# axiom_beta_interface_dummy_v0_8.net
KiCad netlist of a schematic drawn in EAGLE
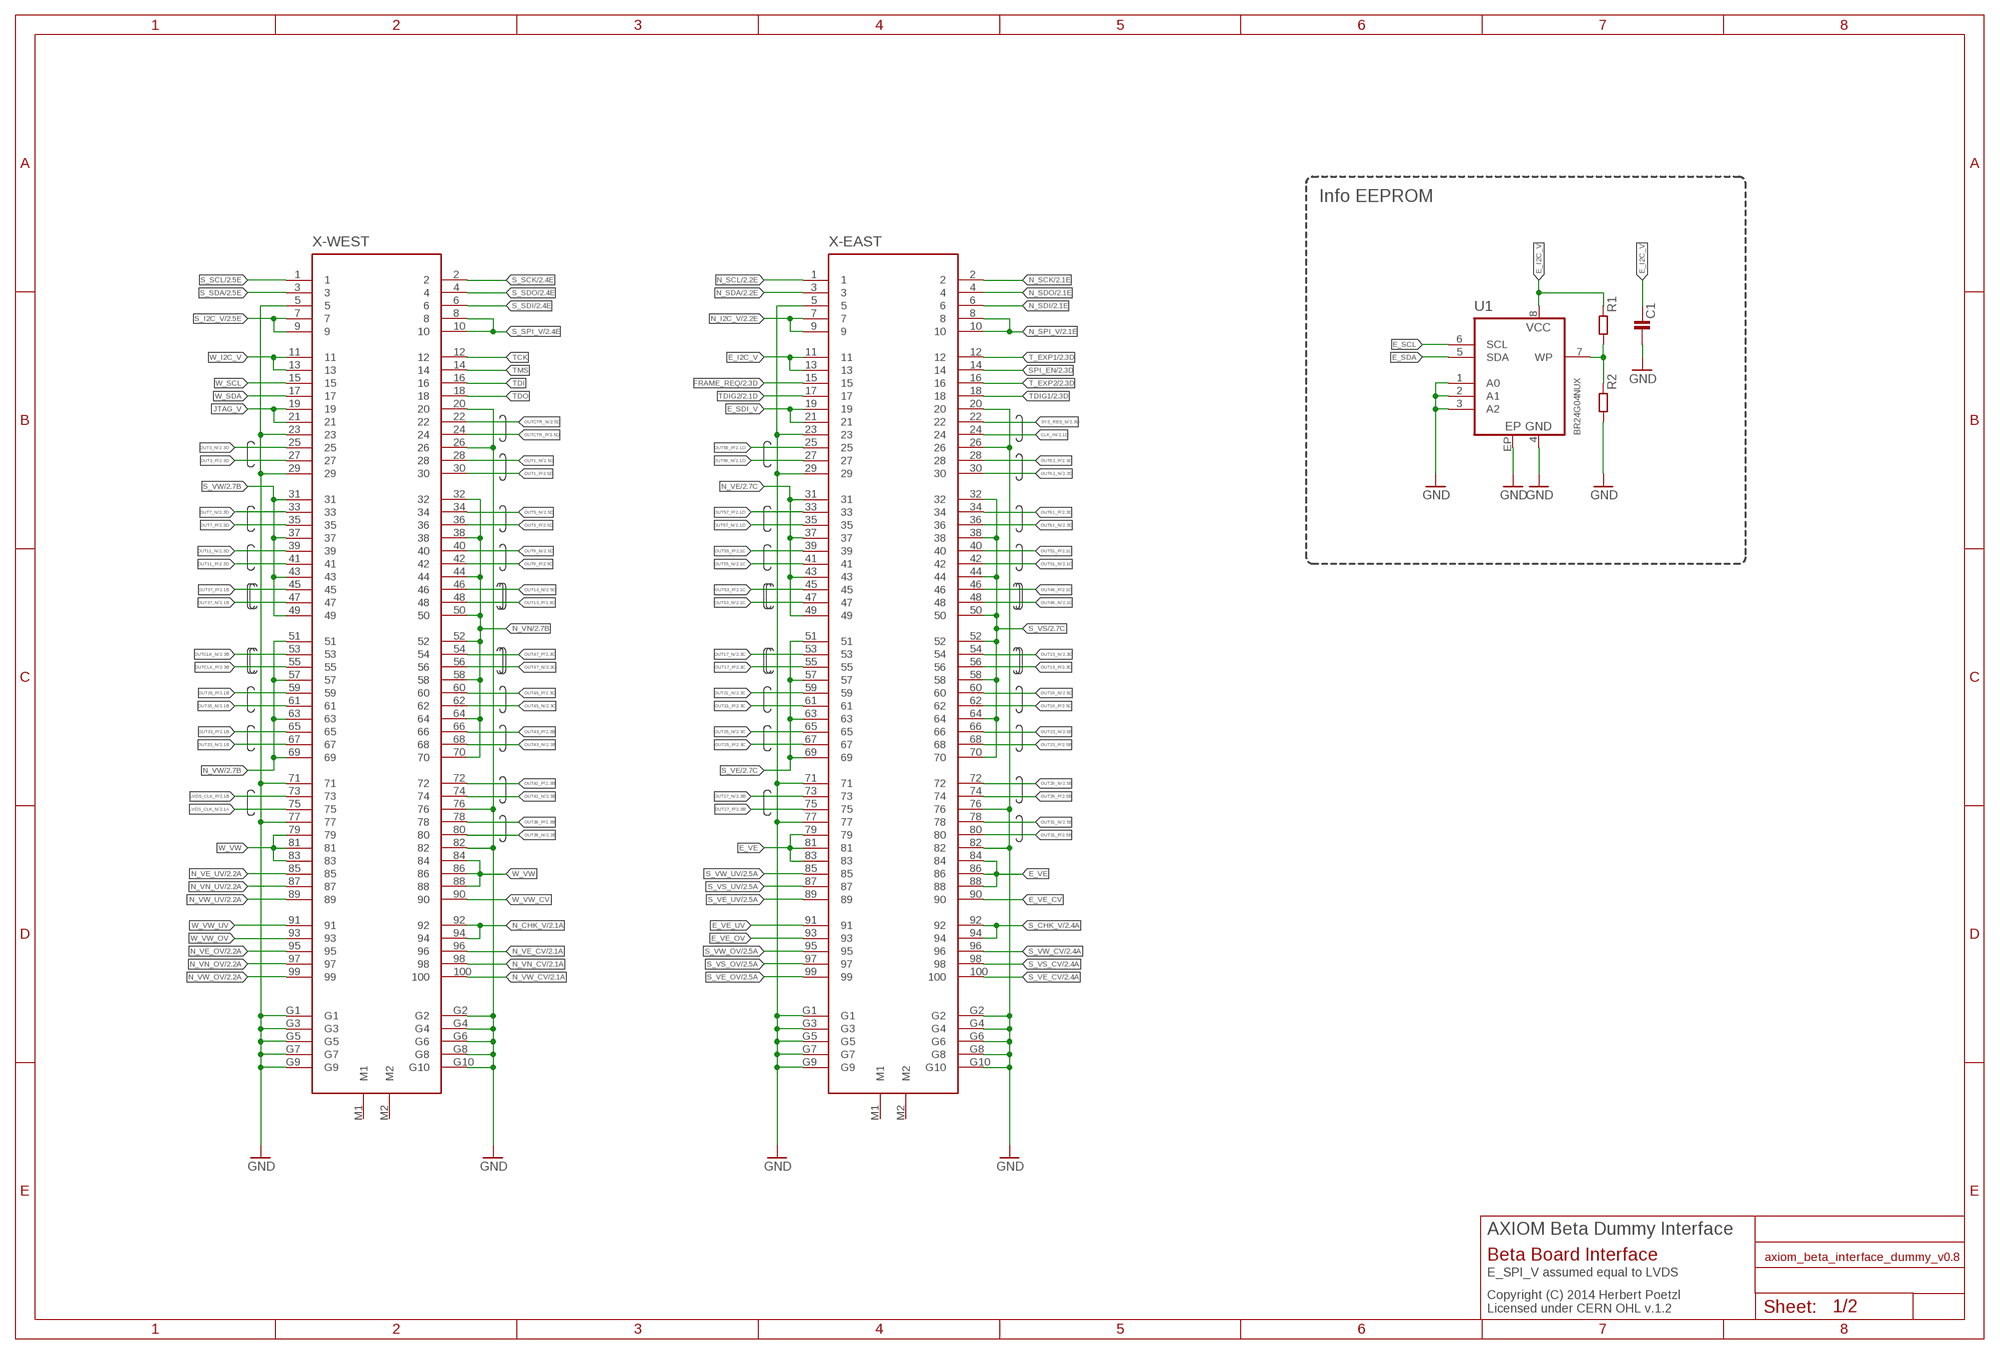
[diagram p0: schematic, sheet 1]
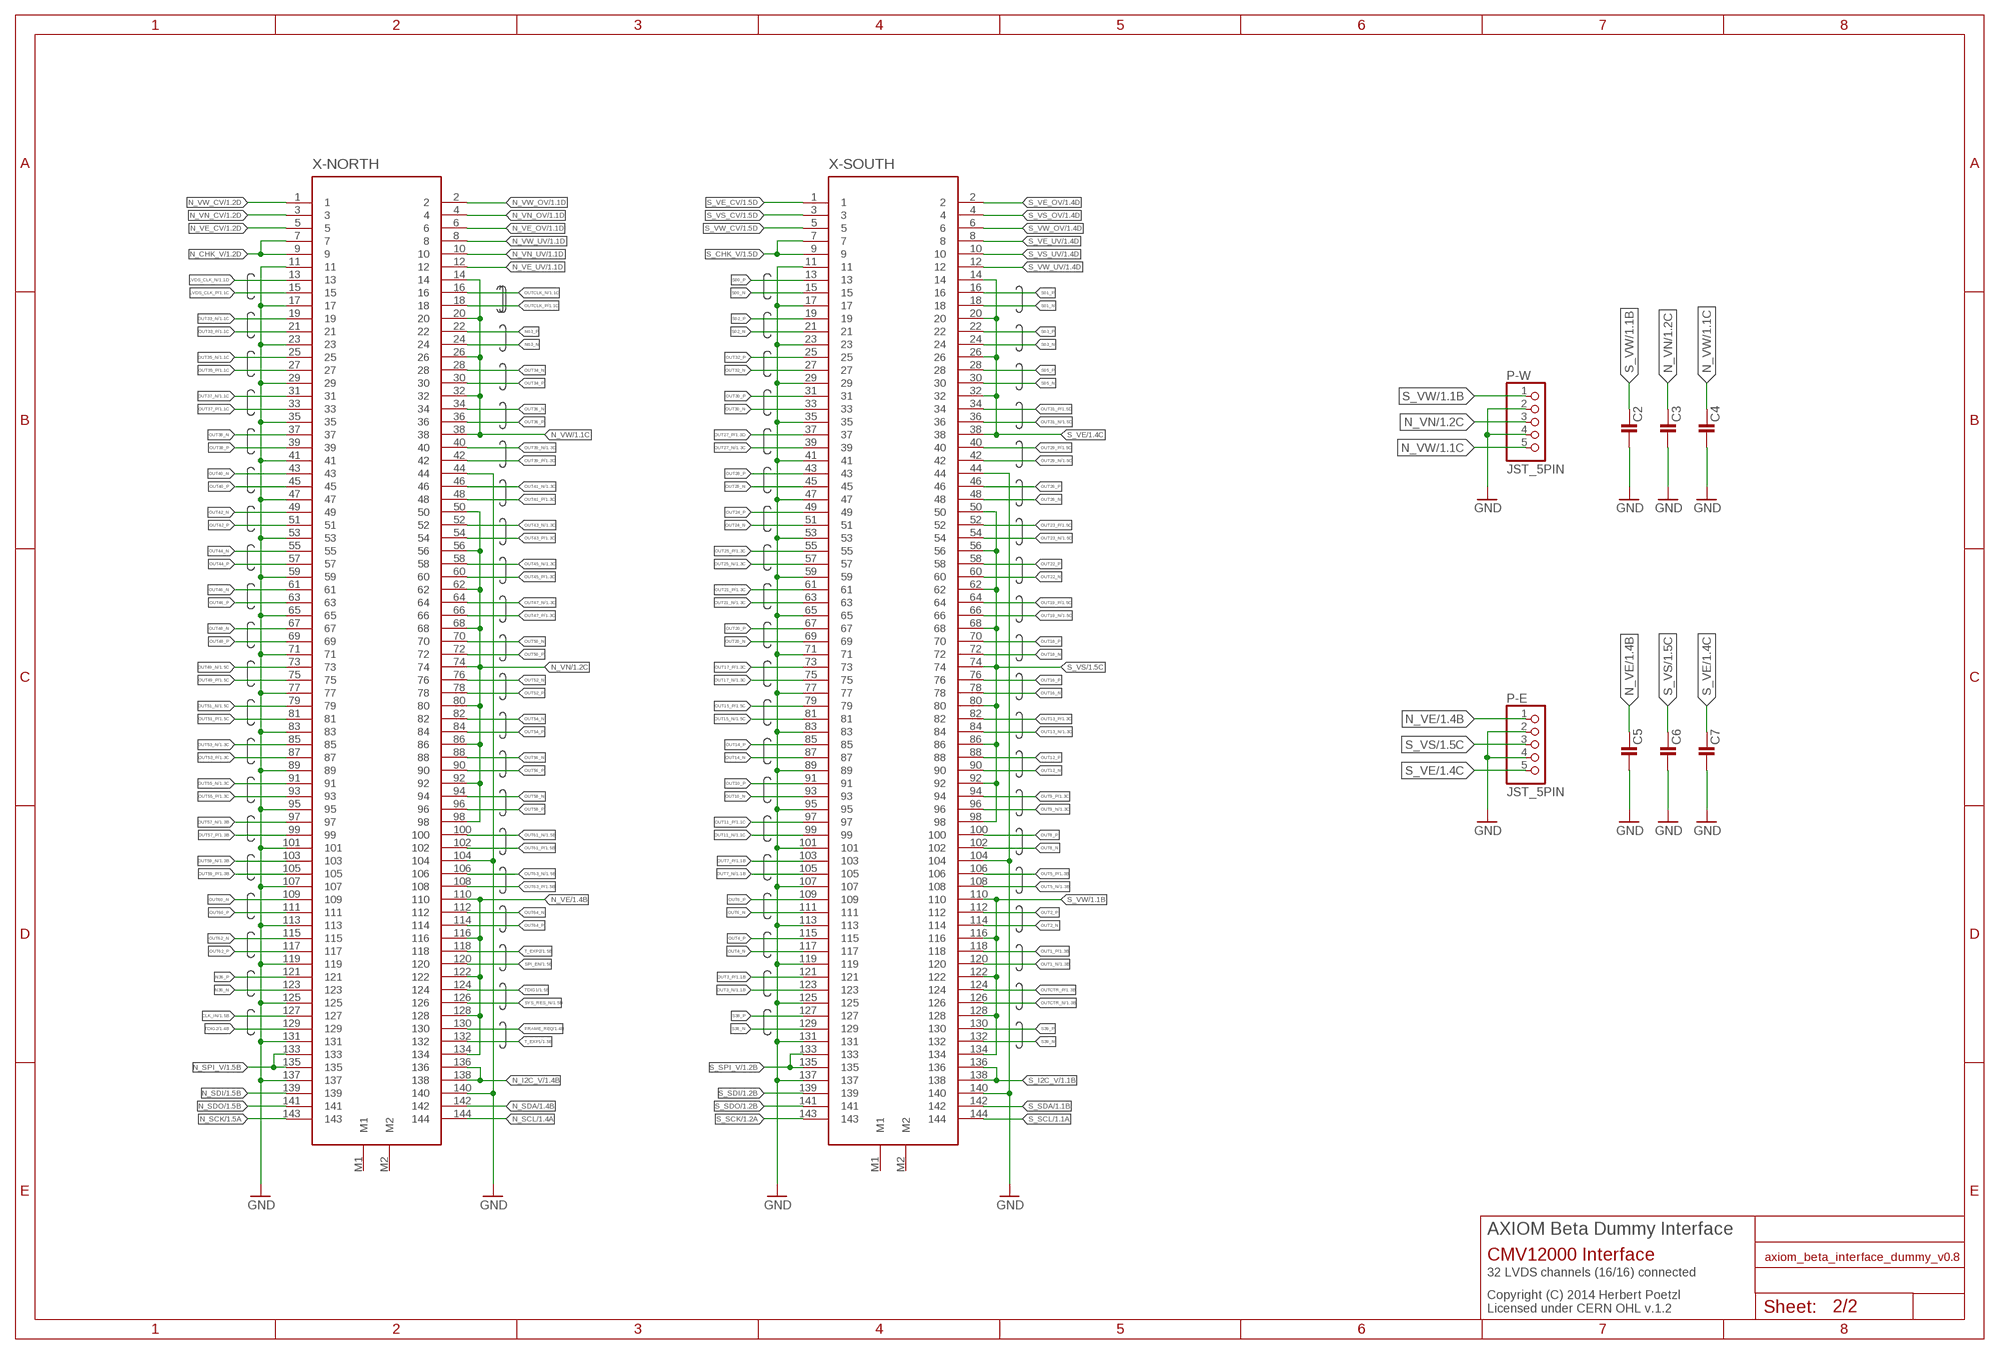
[diagram p1: schematic, sheet 2]

(export (version "E")
  (design (tool "Eeschema 10.0.6"))
  (components
    (comp (ref "C2")
      (value "C1206-B")
      (footprint "eagle-import:1206-B")
      (libsource (lib "eagle-import") (part "C1206-B"))
    )
    (comp (ref "C3")
      (value "C1206-B")
      (footprint "eagle-import:1206-B")
      (libsource (lib "eagle-import") (part "C1206-B"))
    )
    (comp (ref "C4")
      (value "C1206-B")
      (footprint "eagle-import:1206-B")
      (libsource (lib "eagle-import") (part "C1206-B"))
    )
    (comp (ref "C5")
      (value "C1206-B")
      (footprint "eagle-import:1206-B")
      (libsource (lib "eagle-import") (part "C1206-B"))
    )
    (comp (ref "C6")
      (value "C1206-B")
      (footprint "eagle-import:1206-B")
      (libsource (lib "eagle-import") (part "C1206-B"))
    )
    (comp (ref "C7")
      (value "C1206-B")
      (footprint "eagle-import:1206-B")
      (libsource (lib "eagle-import") (part "C1206-B"))
    )
    (comp (ref "P-E")
      (value "JST_5PIN")
      (footprint "eagle-import:JST-PH-5-SMT-RA")
      (libsource (lib "eagle-import") (part "JST_5PIN"))
    )
    (comp (ref "P-W")
      (value "JST_5PIN")
      (footprint "eagle-import:JST-PH-5-SMT-RA")
      (libsource (lib "eagle-import") (part "JST_5PIN"))
    )
    (comp (ref "X-NORTH")
      (value "FX10-144S")
      (footprint "eagle-import:FX10A-144S")
      (libsource (lib "eagle-import") (part "FX10-144S"))
    )
    (comp (ref "X-SOUTH")
      (value "FX10-144S")
      (footprint "eagle-import:FX10A-144S")
      (libsource (lib "eagle-import") (part "FX10-144S"))
    )
    (comp (ref "C1")
      (value "C0402-B")
      (footprint "eagle-import:0402-B")
      (libsource (lib "eagle-import") (part "C0402-B"))
    )
    (comp (ref "R1")
      (value "R0402-B")
      (footprint "eagle-import:0402-B")
      (libsource (lib "eagle-import") (part "R0402-B"))
    )
    (comp (ref "R2")
      (value "R0402-B")
      (footprint "eagle-import:0402-B")
      (libsource (lib "eagle-import") (part "R0402-B"))
    )
    (comp (ref "U1")
      (value "BR24G04NUX")
      (footprint "eagle-import:DFN200X300X100-9N")
      (libsource (lib "eagle-import") (part "BR24G04NUX"))
    )
    (comp (ref "X-EAST")
      (value "FX10-100/10P")
      (footprint "eagle-import:FX10A-100P_10")
      (libsource (lib "eagle-import") (part "FX10-100/10P"))
    )
    (comp (ref "X-WEST")
      (value "FX10-100/10P")
      (footprint "eagle-import:FX10A-100P_10")
      (libsource (lib "eagle-import") (part "FX10-100/10P"))
    )
  )
  (nets
    (net (code "1") (name "CLK_IN") (class "Default")
      (node (ref "X-EAST") (pin "24") (pinfunction "24_24") (pintype "bidirectional"))
      (node (ref "X-NORTH") (pin "127") (pinfunction "127_127") (pintype "bidirectional"))
    )
    (net (code "2") (name "E_I2C_V") (class "Default")
      (node (ref "C1") (pin "1") (pinfunction "1_1") (pintype "passive"))
      (node (ref "R1") (pin "1") (pinfunction "1_1") (pintype "passive"))
      (node (ref "U1") (pin "8") (pinfunction "VCC_8") (pintype "power_in"))
      (node (ref "X-EAST") (pin "11") (pinfunction "11_11") (pintype "bidirectional"))
      (node (ref "X-EAST") (pin "13") (pinfunction "13_13") (pintype "bidirectional"))
    )
    (net (code "3") (name "E_SCL") (class "Default")
      (node (ref "U1") (pin "6") (pinfunction "SCL_6") (pintype "input"))
    )
    (net (code "4") (name "E_SDA") (class "Default")
      (node (ref "U1") (pin "5") (pinfunction "SDA_5") (pintype "bidirectional"))
    )
    (net (code "5") (name "E_SDI_V") (class "Default")
      (node (ref "X-EAST") (pin "19") (pinfunction "19_19") (pintype "bidirectional"))
      (node (ref "X-EAST") (pin "21") (pinfunction "21_21") (pintype "bidirectional"))
    )
    (net (code "6") (name "E_VE") (class "Default")
      (node (ref "X-EAST") (pin "79") (pinfunction "79_79") (pintype "bidirectional"))
      (node (ref "X-EAST") (pin "81") (pinfunction "81_81") (pintype "bidirectional"))
      (node (ref "X-EAST") (pin "83") (pinfunction "83_83") (pintype "bidirectional"))
      (node (ref "X-EAST") (pin "84") (pinfunction "84_84") (pintype "bidirectional"))
      (node (ref "X-EAST") (pin "86") (pinfunction "86_86") (pintype "bidirectional"))
      (node (ref "X-EAST") (pin "88") (pinfunction "88_88") (pintype "bidirectional"))
    )
    (net (code "7") (name "E_VE_CV") (class "Default")
      (node (ref "X-EAST") (pin "90") (pinfunction "90_90") (pintype "bidirectional"))
    )
    (net (code "8") (name "E_VE_OV") (class "Default")
      (node (ref "X-EAST") (pin "93") (pinfunction "93_93") (pintype "bidirectional"))
    )
    (net (code "9") (name "E_VE_UV") (class "Default")
      (node (ref "X-EAST") (pin "91") (pinfunction "91_91") (pintype "bidirectional"))
    )
    (net (code "10") (name "FRAME_REQ") (class "Default")
      (node (ref "X-EAST") (pin "15") (pinfunction "15_15") (pintype "bidirectional"))
      (node (ref "X-NORTH") (pin "130") (pinfunction "130_130") (pintype "bidirectional"))
    )
    (net (code "11") (name "GND") (class "Default")
      (node (ref "C1") (pin "2") (pinfunction "2_2") (pintype "passive"))
      (node (ref "C2") (pin "2") (pinfunction "2_2") (pintype "passive"))
      (node (ref "C3") (pin "2") (pinfunction "2_2") (pintype "passive"))
      (node (ref "C4") (pin "2") (pinfunction "2_2") (pintype "passive"))
      (node (ref "C5") (pin "2") (pinfunction "2_2") (pintype "passive"))
      (node (ref "C6") (pin "2") (pinfunction "2_2") (pintype "passive"))
      (node (ref "C7") (pin "2") (pinfunction "2_2") (pintype "passive"))
      (node (ref "P-E") (pin "2") (pinfunction "2_2") (pintype "passive"))
      (node (ref "P-E") (pin "4") (pinfunction "4_4") (pintype "passive"))
      (node (ref "P-W") (pin "2") (pinfunction "2_2") (pintype "passive"))
      (node (ref "P-W") (pin "4") (pinfunction "4_4") (pintype "passive"))
      (node (ref "R2") (pin "2") (pinfunction "2_2") (pintype "passive"))
      (node (ref "U1") (pin "1") (pinfunction "A0_1") (pintype "input"))
      (node (ref "U1") (pin "2") (pinfunction "A1_2") (pintype "input"))
      (node (ref "U1") (pin "3") (pinfunction "A2_3") (pintype "input"))
      (node (ref "U1") (pin "4") (pinfunction "GND_4") (pintype "passive"))
      (node (ref "U1") (pin "EP") (pinfunction "EP_EP") (pintype "passive"))
      (node (ref "X-EAST") (pin "20") (pinfunction "20_20") (pintype "bidirectional"))
      (node (ref "X-EAST") (pin "23") (pinfunction "23_23") (pintype "bidirectional"))
      (node (ref "X-EAST") (pin "26") (pinfunction "26_26") (pintype "bidirectional"))
      (node (ref "X-EAST") (pin "29") (pinfunction "29_29") (pintype "bidirectional"))
      (node (ref "X-EAST") (pin "5") (pinfunction "5_5") (pintype "bidirectional"))
      (node (ref "X-EAST") (pin "71") (pinfunction "71_71") (pintype "bidirectional"))
      (node (ref "X-EAST") (pin "76") (pinfunction "76_76") (pintype "bidirectional"))
      (node (ref "X-EAST") (pin "77") (pinfunction "77_77") (pintype "bidirectional"))
      (node (ref "X-EAST") (pin "82") (pinfunction "82_82") (pintype "bidirectional"))
      (node (ref "X-EAST") (pin "G1") (pinfunction "G1_G1") (pintype "bidirectional"))
      (node (ref "X-EAST") (pin "G10") (pinfunction "G10_G10") (pintype "bidirectional"))
      (node (ref "X-EAST") (pin "G2") (pinfunction "G2_G2") (pintype "bidirectional"))
      (node (ref "X-EAST") (pin "G3") (pinfunction "G3_G3") (pintype "bidirectional"))
      (node (ref "X-EAST") (pin "G4") (pinfunction "G4_G4") (pintype "bidirectional"))
      (node (ref "X-EAST") (pin "G5") (pinfunction "G5_G5") (pintype "bidirectional"))
      (node (ref "X-EAST") (pin "G6") (pinfunction "G6_G6") (pintype "bidirectional"))
      (node (ref "X-EAST") (pin "G7") (pinfunction "G7_G7") (pintype "bidirectional"))
      (node (ref "X-EAST") (pin "G8") (pinfunction "G8_G8") (pintype "bidirectional"))
      (node (ref "X-EAST") (pin "G9") (pinfunction "G9_G9") (pintype "bidirectional"))
      (node (ref "X-NORTH") (pin "101") (pinfunction "101_101") (pintype "bidirectional"))
      (node (ref "X-NORTH") (pin "104") (pinfunction "104_104") (pintype "bidirectional"))
      (node (ref "X-NORTH") (pin "107") (pinfunction "107_107") (pintype "bidirectional"))
      (node (ref "X-NORTH") (pin "11") (pinfunction "11_11") (pintype "bidirectional"))
      (node (ref "X-NORTH") (pin "113") (pinfunction "113_113") (pintype "bidirectional"))
      (node (ref "X-NORTH") (pin "119") (pinfunction "119_119") (pintype "bidirectional"))
      (node (ref "X-NORTH") (pin "125") (pinfunction "125_125") (pintype "bidirectional"))
      (node (ref "X-NORTH") (pin "131") (pinfunction "131_131") (pintype "bidirectional"))
      (node (ref "X-NORTH") (pin "137") (pinfunction "137_137") (pintype "bidirectional"))
      (node (ref "X-NORTH") (pin "140") (pinfunction "140_140") (pintype "bidirectional"))
      (node (ref "X-NORTH") (pin "17") (pinfunction "17_17") (pintype "bidirectional"))
      (node (ref "X-NORTH") (pin "23") (pinfunction "23_23") (pintype "bidirectional"))
      (node (ref "X-NORTH") (pin "29") (pinfunction "29_29") (pintype "bidirectional"))
      (node (ref "X-NORTH") (pin "35") (pinfunction "35_35") (pintype "bidirectional"))
      (node (ref "X-NORTH") (pin "41") (pinfunction "41_41") (pintype "bidirectional"))
      (node (ref "X-NORTH") (pin "44") (pinfunction "44_44") (pintype "bidirectional"))
      (node (ref "X-NORTH") (pin "47") (pinfunction "47_47") (pintype "bidirectional"))
      (node (ref "X-NORTH") (pin "53") (pinfunction "53_53") (pintype "bidirectional"))
      (node (ref "X-NORTH") (pin "59") (pinfunction "59_59") (pintype "bidirectional"))
      (node (ref "X-NORTH") (pin "65") (pinfunction "65_65") (pintype "bidirectional"))
      (node (ref "X-NORTH") (pin "71") (pinfunction "71_71") (pintype "bidirectional"))
      (node (ref "X-NORTH") (pin "77") (pinfunction "77_77") (pintype "bidirectional"))
      (node (ref "X-NORTH") (pin "83") (pinfunction "83_83") (pintype "bidirectional"))
      (node (ref "X-NORTH") (pin "89") (pinfunction "89_89") (pintype "bidirectional"))
      (node (ref "X-NORTH") (pin "95") (pinfunction "95_95") (pintype "bidirectional"))
      (node (ref "X-SOUTH") (pin "101") (pinfunction "101_101") (pintype "bidirectional"))
      (node (ref "X-SOUTH") (pin "104") (pinfunction "104_104") (pintype "bidirectional"))
      (node (ref "X-SOUTH") (pin "107") (pinfunction "107_107") (pintype "bidirectional"))
      (node (ref "X-SOUTH") (pin "11") (pinfunction "11_11") (pintype "bidirectional"))
      (node (ref "X-SOUTH") (pin "113") (pinfunction "113_113") (pintype "bidirectional"))
      (node (ref "X-SOUTH") (pin "119") (pinfunction "119_119") (pintype "bidirectional"))
      (node (ref "X-SOUTH") (pin "125") (pinfunction "125_125") (pintype "bidirectional"))
      (node (ref "X-SOUTH") (pin "131") (pinfunction "131_131") (pintype "bidirectional"))
      (node (ref "X-SOUTH") (pin "137") (pinfunction "137_137") (pintype "bidirectional"))
      (node (ref "X-SOUTH") (pin "140") (pinfunction "140_140") (pintype "bidirectional"))
      (node (ref "X-SOUTH") (pin "17") (pinfunction "17_17") (pintype "bidirectional"))
      (node (ref "X-SOUTH") (pin "23") (pinfunction "23_23") (pintype "bidirectional"))
      (node (ref "X-SOUTH") (pin "29") (pinfunction "29_29") (pintype "bidirectional"))
      (node (ref "X-SOUTH") (pin "35") (pinfunction "35_35") (pintype "bidirectional"))
      (node (ref "X-SOUTH") (pin "41") (pinfunction "41_41") (pintype "bidirectional"))
      (node (ref "X-SOUTH") (pin "44") (pinfunction "44_44") (pintype "bidirectional"))
      (node (ref "X-SOUTH") (pin "47") (pinfunction "47_47") (pintype "bidirectional"))
      (node (ref "X-SOUTH") (pin "53") (pinfunction "53_53") (pintype "bidirectional"))
      (node (ref "X-SOUTH") (pin "59") (pinfunction "59_59") (pintype "bidirectional"))
      (node (ref "X-SOUTH") (pin "65") (pinfunction "65_65") (pintype "bidirectional"))
      (node (ref "X-SOUTH") (pin "71") (pinfunction "71_71") (pintype "bidirectional"))
      (node (ref "X-SOUTH") (pin "77") (pinfunction "77_77") (pintype "bidirectional"))
      (node (ref "X-SOUTH") (pin "83") (pinfunction "83_83") (pintype "bidirectional"))
      (node (ref "X-SOUTH") (pin "89") (pinfunction "89_89") (pintype "bidirectional"))
      (node (ref "X-SOUTH") (pin "95") (pinfunction "95_95") (pintype "bidirectional"))
      (node (ref "X-WEST") (pin "20") (pinfunction "20_20") (pintype "bidirectional"))
      (node (ref "X-WEST") (pin "23") (pinfunction "23_23") (pintype "bidirectional"))
      (node (ref "X-WEST") (pin "26") (pinfunction "26_26") (pintype "bidirectional"))
      (node (ref "X-WEST") (pin "29") (pinfunction "29_29") (pintype "bidirectional"))
      (node (ref "X-WEST") (pin "5") (pinfunction "5_5") (pintype "bidirectional"))
      (node (ref "X-WEST") (pin "71") (pinfunction "71_71") (pintype "bidirectional"))
      (node (ref "X-WEST") (pin "76") (pinfunction "76_76") (pintype "bidirectional"))
      (node (ref "X-WEST") (pin "77") (pinfunction "77_77") (pintype "bidirectional"))
      (node (ref "X-WEST") (pin "82") (pinfunction "82_82") (pintype "bidirectional"))
      (node (ref "X-WEST") (pin "G1") (pinfunction "G1_G1") (pintype "bidirectional"))
      (node (ref "X-WEST") (pin "G10") (pinfunction "G10_G10") (pintype "bidirectional"))
      (node (ref "X-WEST") (pin "G2") (pinfunction "G2_G2") (pintype "bidirectional"))
      (node (ref "X-WEST") (pin "G3") (pinfunction "G3_G3") (pintype "bidirectional"))
      (node (ref "X-WEST") (pin "G4") (pinfunction "G4_G4") (pintype "bidirectional"))
      (node (ref "X-WEST") (pin "G5") (pinfunction "G5_G5") (pintype "bidirectional"))
      (node (ref "X-WEST") (pin "G6") (pinfunction "G6_G6") (pintype "bidirectional"))
      (node (ref "X-WEST") (pin "G7") (pinfunction "G7_G7") (pintype "bidirectional"))
      (node (ref "X-WEST") (pin "G8") (pinfunction "G8_G8") (pintype "bidirectional"))
      (node (ref "X-WEST") (pin "G9") (pinfunction "G9_G9") (pintype "bidirectional"))
    )
    (net (code "12") (name "JTAG_V") (class "Default")
      (node (ref "X-WEST") (pin "19") (pinfunction "19_19") (pintype "bidirectional"))
      (node (ref "X-WEST") (pin "21") (pinfunction "21_21") (pintype "bidirectional"))
    )
    (net (code "13") (name "LVDS_CLK_N") (class "Default")
      (node (ref "X-NORTH") (pin "13") (pinfunction "13_13") (pintype "bidirectional"))
      (node (ref "X-WEST") (pin "75") (pinfunction "75_75") (pintype "bidirectional"))
    )
    (net (code "14") (name "LVDS_CLK_P") (class "Default")
      (node (ref "X-NORTH") (pin "15") (pinfunction "15_15") (pintype "bidirectional"))
      (node (ref "X-WEST") (pin "73") (pinfunction "73_73") (pintype "bidirectional"))
    )
    (net (code "15") (name "N03_N") (class "Default")
      (node (ref "X-NORTH") (pin "24") (pinfunction "24_24") (pintype "bidirectional"))
    )
    (net (code "16") (name "N03_P") (class "Default")
      (node (ref "X-NORTH") (pin "22") (pinfunction "22_22") (pintype "bidirectional"))
    )
    (net (code "17") (name "N36_N") (class "Default")
      (node (ref "X-NORTH") (pin "123") (pinfunction "123_123") (pintype "bidirectional"))
    )
    (net (code "18") (name "N36_P") (class "Default")
      (node (ref "X-NORTH") (pin "121") (pinfunction "121_121") (pintype "bidirectional"))
    )
    (net (code "19") (name "N_CHK_V") (class "Default")
      (node (ref "X-NORTH") (pin "7") (pinfunction "7_7") (pintype "bidirectional"))
      (node (ref "X-NORTH") (pin "9") (pinfunction "9_9") (pintype "bidirectional"))
      (node (ref "X-WEST") (pin "92") (pinfunction "92_92") (pintype "bidirectional"))
      (node (ref "X-WEST") (pin "94") (pinfunction "94_94") (pintype "bidirectional"))
    )
    (net (code "20") (name "N_I2C_V") (class "Default")
      (node (ref "X-EAST") (pin "7") (pinfunction "7_7") (pintype "bidirectional"))
      (node (ref "X-EAST") (pin "9") (pinfunction "9_9") (pintype "bidirectional"))
      (node (ref "X-NORTH") (pin "136") (pinfunction "136_136") (pintype "bidirectional"))
      (node (ref "X-NORTH") (pin "138") (pinfunction "138_138") (pintype "bidirectional"))
    )
    (net (code "21") (name "N_SCK") (class "Default")
      (node (ref "X-EAST") (pin "2") (pinfunction "2_2") (pintype "bidirectional"))
      (node (ref "X-NORTH") (pin "143") (pinfunction "143_143") (pintype "bidirectional"))
    )
    (net (code "22") (name "N_SCL") (class "Default")
      (node (ref "X-EAST") (pin "1") (pinfunction "1_1") (pintype "bidirectional"))
      (node (ref "X-NORTH") (pin "144") (pinfunction "144_144") (pintype "bidirectional"))
    )
    (net (code "23") (name "N_SDA") (class "Default")
      (node (ref "X-EAST") (pin "3") (pinfunction "3_3") (pintype "bidirectional"))
      (node (ref "X-NORTH") (pin "142") (pinfunction "142_142") (pintype "bidirectional"))
    )
    (net (code "24") (name "N_SDI") (class "Default")
      (node (ref "X-EAST") (pin "6") (pinfunction "6_6") (pintype "bidirectional"))
      (node (ref "X-NORTH") (pin "139") (pinfunction "139_139") (pintype "bidirectional"))
    )
    (net (code "25") (name "N_SDO") (class "Default")
      (node (ref "X-EAST") (pin "4") (pinfunction "4_4") (pintype "bidirectional"))
      (node (ref "X-NORTH") (pin "141") (pinfunction "141_141") (pintype "bidirectional"))
    )
    (net (code "26") (name "N_SPI_V") (class "Default")
      (node (ref "X-EAST") (pin "10") (pinfunction "10_10") (pintype "bidirectional"))
      (node (ref "X-EAST") (pin "8") (pinfunction "8_8") (pintype "bidirectional"))
      (node (ref "X-NORTH") (pin "133") (pinfunction "133_133") (pintype "bidirectional"))
      (node (ref "X-NORTH") (pin "135") (pinfunction "135_135") (pintype "bidirectional"))
    )
    (net (code "27") (name "N_VE") (class "Default")
      (node (ref "C5") (pin "1") (pinfunction "1_1") (pintype "passive"))
      (node (ref "P-E") (pin "1") (pinfunction "1_1") (pintype "passive"))
      (node (ref "X-EAST") (pin "31") (pinfunction "31_31") (pintype "bidirectional"))
      (node (ref "X-EAST") (pin "37") (pinfunction "37_37") (pintype "bidirectional"))
      (node (ref "X-EAST") (pin "43") (pinfunction "43_43") (pintype "bidirectional"))
      (node (ref "X-EAST") (pin "49") (pinfunction "49_49") (pintype "bidirectional"))
      (node (ref "X-NORTH") (pin "110") (pinfunction "110_110") (pintype "bidirectional"))
      (node (ref "X-NORTH") (pin "116") (pinfunction "116_116") (pintype "bidirectional"))
      (node (ref "X-NORTH") (pin "122") (pinfunction "122_122") (pintype "bidirectional"))
      (node (ref "X-NORTH") (pin "128") (pinfunction "128_128") (pintype "bidirectional"))
      (node (ref "X-NORTH") (pin "134") (pinfunction "134_134") (pintype "bidirectional"))
    )
    (net (code "28") (name "N_VE_CV") (class "Default")
      (node (ref "X-NORTH") (pin "5") (pinfunction "5_5") (pintype "bidirectional"))
      (node (ref "X-WEST") (pin "96") (pinfunction "96_96") (pintype "bidirectional"))
    )
    (net (code "29") (name "N_VE_OV") (class "Default")
      (node (ref "X-NORTH") (pin "6") (pinfunction "6_6") (pintype "bidirectional"))
      (node (ref "X-WEST") (pin "95") (pinfunction "95_95") (pintype "bidirectional"))
    )
    (net (code "30") (name "N_VE_UV") (class "Default")
      (node (ref "X-NORTH") (pin "12") (pinfunction "12_12") (pintype "bidirectional"))
      (node (ref "X-WEST") (pin "85") (pinfunction "85_85") (pintype "bidirectional"))
    )
    (net (code "31") (name "N_VN") (class "Default")
      (node (ref "C3") (pin "1") (pinfunction "1_1") (pintype "passive"))
      (node (ref "P-W") (pin "3") (pinfunction "3_3") (pintype "passive"))
      (node (ref "X-NORTH") (pin "50") (pinfunction "50_50") (pintype "bidirectional"))
      (node (ref "X-NORTH") (pin "56") (pinfunction "56_56") (pintype "bidirectional"))
      (node (ref "X-NORTH") (pin "62") (pinfunction "62_62") (pintype "bidirectional"))
      (node (ref "X-NORTH") (pin "68") (pinfunction "68_68") (pintype "bidirectional"))
      (node (ref "X-NORTH") (pin "74") (pinfunction "74_74") (pintype "bidirectional"))
      (node (ref "X-NORTH") (pin "80") (pinfunction "80_80") (pintype "bidirectional"))
      (node (ref "X-NORTH") (pin "86") (pinfunction "86_86") (pintype "bidirectional"))
      (node (ref "X-NORTH") (pin "92") (pinfunction "92_92") (pintype "bidirectional"))
      (node (ref "X-NORTH") (pin "98") (pinfunction "98_98") (pintype "bidirectional"))
      (node (ref "X-WEST") (pin "32") (pinfunction "32_32") (pintype "bidirectional"))
      (node (ref "X-WEST") (pin "38") (pinfunction "38_38") (pintype "bidirectional"))
      (node (ref "X-WEST") (pin "44") (pinfunction "44_44") (pintype "bidirectional"))
      (node (ref "X-WEST") (pin "50") (pinfunction "50_50") (pintype "bidirectional"))
      (node (ref "X-WEST") (pin "52") (pinfunction "52_52") (pintype "bidirectional"))
      (node (ref "X-WEST") (pin "58") (pinfunction "58_58") (pintype "bidirectional"))
      (node (ref "X-WEST") (pin "64") (pinfunction "64_64") (pintype "bidirectional"))
      (node (ref "X-WEST") (pin "70") (pinfunction "70_70") (pintype "bidirectional"))
    )
    (net (code "32") (name "N_VN_CV") (class "Default")
      (node (ref "X-NORTH") (pin "3") (pinfunction "3_3") (pintype "bidirectional"))
      (node (ref "X-WEST") (pin "98") (pinfunction "98_98") (pintype "bidirectional"))
    )
    (net (code "33") (name "N_VN_OV") (class "Default")
      (node (ref "X-NORTH") (pin "4") (pinfunction "4_4") (pintype "bidirectional"))
      (node (ref "X-WEST") (pin "97") (pinfunction "97_97") (pintype "bidirectional"))
    )
    (net (code "34") (name "N_VN_UV") (class "Default")
      (node (ref "X-NORTH") (pin "10") (pinfunction "10_10") (pintype "bidirectional"))
      (node (ref "X-WEST") (pin "87") (pinfunction "87_87") (pintype "bidirectional"))
    )
    (net (code "35") (name "N_VW") (class "Default")
      (node (ref "C4") (pin "1") (pinfunction "1_1") (pintype "passive"))
      (node (ref "P-W") (pin "5") (pinfunction "5_5") (pintype "passive"))
      (node (ref "X-NORTH") (pin "14") (pinfunction "14_14") (pintype "bidirectional"))
      (node (ref "X-NORTH") (pin "20") (pinfunction "20_20") (pintype "bidirectional"))
      (node (ref "X-NORTH") (pin "26") (pinfunction "26_26") (pintype "bidirectional"))
      (node (ref "X-NORTH") (pin "32") (pinfunction "32_32") (pintype "bidirectional"))
      (node (ref "X-NORTH") (pin "38") (pinfunction "38_38") (pintype "bidirectional"))
      (node (ref "X-WEST") (pin "51") (pinfunction "51_51") (pintype "bidirectional"))
      (node (ref "X-WEST") (pin "57") (pinfunction "57_57") (pintype "bidirectional"))
      (node (ref "X-WEST") (pin "63") (pinfunction "63_63") (pintype "bidirectional"))
      (node (ref "X-WEST") (pin "69") (pinfunction "69_69") (pintype "bidirectional"))
    )
    (net (code "36") (name "N_VW_CV") (class "Default")
      (node (ref "X-NORTH") (pin "1") (pinfunction "1_1") (pintype "bidirectional"))
      (node (ref "X-WEST") (pin "100") (pinfunction "100_100") (pintype "bidirectional"))
    )
    (net (code "37") (name "N_VW_OV") (class "Default")
      (node (ref "X-NORTH") (pin "2") (pinfunction "2_2") (pintype "bidirectional"))
      (node (ref "X-WEST") (pin "99") (pinfunction "99_99") (pintype "bidirectional"))
    )
    (net (code "38") (name "N_VW_UV") (class "Default")
      (node (ref "X-NORTH") (pin "8") (pinfunction "8_8") (pintype "bidirectional"))
      (node (ref "X-WEST") (pin "89") (pinfunction "89_89") (pintype "bidirectional"))
    )
    (net (code "39") (name "Net-(U1-WP)") (class "Default")
      (node (ref "R1") (pin "2") (pinfunction "2_2") (pintype "passive"))
      (node (ref "R2") (pin "1") (pinfunction "1_1") (pintype "passive"))
      (node (ref "U1") (pin "7") (pinfunction "WP_7") (pintype "input"))
    )
    (net (code "40") (name "OUT1_N") (class "Default")
      (node (ref "X-SOUTH") (pin "120") (pinfunction "120_120") (pintype "bidirectional"))
      (node (ref "X-WEST") (pin "28") (pinfunction "28_28") (pintype "bidirectional"))
    )
    (net (code "41") (name "OUT1_P") (class "Default")
      (node (ref "X-SOUTH") (pin "118") (pinfunction "118_118") (pintype "bidirectional"))
      (node (ref "X-WEST") (pin "30") (pinfunction "30_30") (pintype "bidirectional"))
    )
    (net (code "42") (name "OUT2_N") (class "Default")
      (node (ref "X-SOUTH") (pin "114") (pinfunction "114_114") (pintype "bidirectional"))
    )
    (net (code "43") (name "OUT2_P") (class "Default")
      (node (ref "X-SOUTH") (pin "112") (pinfunction "112_112") (pintype "bidirectional"))
    )
    (net (code "44") (name "OUT3_N") (class "Default")
      (node (ref "X-SOUTH") (pin "123") (pinfunction "123_123") (pintype "bidirectional"))
      (node (ref "X-WEST") (pin "25") (pinfunction "25_25") (pintype "bidirectional"))
    )
    (net (code "45") (name "OUT3_P") (class "Default")
      (node (ref "X-SOUTH") (pin "121") (pinfunction "121_121") (pintype "bidirectional"))
      (node (ref "X-WEST") (pin "27") (pinfunction "27_27") (pintype "bidirectional"))
    )
    (net (code "46") (name "OUT4_N") (class "Default")
      (node (ref "X-SOUTH") (pin "117") (pinfunction "117_117") (pintype "bidirectional"))
    )
    (net (code "47") (name "OUT4_P") (class "Default")
      (node (ref "X-SOUTH") (pin "115") (pinfunction "115_115") (pintype "bidirectional"))
    )
    (net (code "48") (name "OUT5_N") (class "Default")
      (node (ref "X-SOUTH") (pin "108") (pinfunction "108_108") (pintype "bidirectional"))
      (node (ref "X-WEST") (pin "34") (pinfunction "34_34") (pintype "bidirectional"))
    )
    (net (code "49") (name "OUT5_P") (class "Default")
      (node (ref "X-SOUTH") (pin "106") (pinfunction "106_106") (pintype "bidirectional"))
      (node (ref "X-WEST") (pin "36") (pinfunction "36_36") (pintype "bidirectional"))
    )
    (net (code "50") (name "OUT6_N") (class "Default")
      (node (ref "X-SOUTH") (pin "111") (pinfunction "111_111") (pintype "bidirectional"))
    )
    (net (code "51") (name "OUT6_P") (class "Default")
      (node (ref "X-SOUTH") (pin "109") (pinfunction "109_109") (pintype "bidirectional"))
    )
    (net (code "52") (name "OUT7_N") (class "Default")
      (node (ref "X-SOUTH") (pin "105") (pinfunction "105_105") (pintype "bidirectional"))
      (node (ref "X-WEST") (pin "33") (pinfunction "33_33") (pintype "bidirectional"))
    )
    (net (code "53") (name "OUT7_P") (class "Default")
      (node (ref "X-SOUTH") (pin "103") (pinfunction "103_103") (pintype "bidirectional"))
      (node (ref "X-WEST") (pin "35") (pinfunction "35_35") (pintype "bidirectional"))
    )
    (net (code "54") (name "OUT8_N") (class "Default")
      (node (ref "X-SOUTH") (pin "102") (pinfunction "102_102") (pintype "bidirectional"))
    )
    (net (code "55") (name "OUT8_P") (class "Default")
      (node (ref "X-SOUTH") (pin "100") (pinfunction "100_100") (pintype "bidirectional"))
    )
    (net (code "56") (name "OUT9_N") (class "Default")
      (node (ref "X-SOUTH") (pin "96") (pinfunction "96_96") (pintype "bidirectional"))
      (node (ref "X-WEST") (pin "40") (pinfunction "40_40") (pintype "bidirectional"))
    )
    (net (code "57") (name "OUT9_P") (class "Default")
      (node (ref "X-SOUTH") (pin "94") (pinfunction "94_94") (pintype "bidirectional"))
      (node (ref "X-WEST") (pin "42") (pinfunction "42_42") (pintype "bidirectional"))
    )
    (net (code "58") (name "OUT10_N") (class "Default")
      (node (ref "X-SOUTH") (pin "93") (pinfunction "93_93") (pintype "bidirectional"))
    )
    (net (code "59") (name "OUT10_P") (class "Default")
      (node (ref "X-SOUTH") (pin "91") (pinfunction "91_91") (pintype "bidirectional"))
    )
    (net (code "60") (name "OUT11_N") (class "Default")
      (node (ref "X-SOUTH") (pin "99") (pinfunction "99_99") (pintype "bidirectional"))
      (node (ref "X-WEST") (pin "39") (pinfunction "39_39") (pintype "bidirectional"))
    )
    (net (code "61") (name "OUT11_P") (class "Default")
      (node (ref "X-SOUTH") (pin "97") (pinfunction "97_97") (pintype "bidirectional"))
      (node (ref "X-WEST") (pin "41") (pinfunction "41_41") (pintype "bidirectional"))
    )
    (net (code "62") (name "OUT12_N") (class "Default")
      (node (ref "X-SOUTH") (pin "90") (pinfunction "90_90") (pintype "bidirectional"))
    )
    (net (code "63") (name "OUT12_P") (class "Default")
      (node (ref "X-SOUTH") (pin "88") (pinfunction "88_88") (pintype "bidirectional"))
    )
    (net (code "64") (name "OUT13_N") (class "Default")
      (node (ref "X-SOUTH") (pin "84") (pinfunction "84_84") (pintype "bidirectional"))
      (node (ref "X-WEST") (pin "46") (pinfunction "46_46") (pintype "bidirectional"))
    )
    (net (code "65") (name "OUT13_P") (class "Default")
      (node (ref "X-SOUTH") (pin "82") (pinfunction "82_82") (pintype "bidirectional"))
      (node (ref "X-WEST") (pin "48") (pinfunction "48_48") (pintype "bidirectional"))
    )
    (net (code "66") (name "OUT14_N") (class "Default")
      (node (ref "X-SOUTH") (pin "87") (pinfunction "87_87") (pintype "bidirectional"))
    )
    (net (code "67") (name "OUT14_P") (class "Default")
      (node (ref "X-SOUTH") (pin "85") (pinfunction "85_85") (pintype "bidirectional"))
    )
    (net (code "68") (name "OUT15_N") (class "Default")
      (node (ref "X-EAST") (pin "54") (pinfunction "54_54") (pintype "bidirectional"))
      (node (ref "X-SOUTH") (pin "81") (pinfunction "81_81") (pintype "bidirectional"))
    )
    (net (code "69") (name "OUT15_P") (class "Default")
      (node (ref "X-EAST") (pin "56") (pinfunction "56_56") (pintype "bidirectional"))
      (node (ref "X-SOUTH") (pin "79") (pinfunction "79_79") (pintype "bidirectional"))
    )
    (net (code "70") (name "OUT16_N") (class "Default")
      (node (ref "X-SOUTH") (pin "78") (pinfunction "78_78") (pintype "bidirectional"))
    )
    (net (code "71") (name "OUT16_P") (class "Default")
      (node (ref "X-SOUTH") (pin "76") (pinfunction "76_76") (pintype "bidirectional"))
    )
    (net (code "72") (name "OUT17_N") (class "Default")
      (node (ref "X-EAST") (pin "53") (pinfunction "53_53") (pintype "bidirectional"))
      (node (ref "X-SOUTH") (pin "75") (pinfunction "75_75") (pintype "bidirectional"))
    )
    (net (code "73") (name "OUT17_P") (class "Default")
      (node (ref "X-EAST") (pin "55") (pinfunction "55_55") (pintype "bidirectional"))
      (node (ref "X-SOUTH") (pin "73") (pinfunction "73_73") (pintype "bidirectional"))
    )
    (net (code "74") (name "OUT18_N") (class "Default")
      (node (ref "X-SOUTH") (pin "72") (pinfunction "72_72") (pintype "bidirectional"))
    )
    (net (code "75") (name "OUT18_P") (class "Default")
      (node (ref "X-SOUTH") (pin "70") (pinfunction "70_70") (pintype "bidirectional"))
    )
    (net (code "76") (name "OUT19_N") (class "Default")
      (node (ref "X-EAST") (pin "60") (pinfunction "60_60") (pintype "bidirectional"))
      (node (ref "X-SOUTH") (pin "66") (pinfunction "66_66") (pintype "bidirectional"))
    )
    (net (code "77") (name "OUT19_P") (class "Default")
      (node (ref "X-EAST") (pin "62") (pinfunction "62_62") (pintype "bidirectional"))
      (node (ref "X-SOUTH") (pin "64") (pinfunction "64_64") (pintype "bidirectional"))
    )
    (net (code "78") (name "OUT20_N") (class "Default")
      (node (ref "X-SOUTH") (pin "69") (pinfunction "69_69") (pintype "bidirectional"))
    )
    (net (code "79") (name "OUT20_P") (class "Default")
      (node (ref "X-SOUTH") (pin "67") (pinfunction "67_67") (pintype "bidirectional"))
    )
    (net (code "80") (name "OUT21_N") (class "Default")
      (node (ref "X-EAST") (pin "59") (pinfunction "59_59") (pintype "bidirectional"))
      (node (ref "X-SOUTH") (pin "63") (pinfunction "63_63") (pintype "bidirectional"))
    )
    (net (code "81") (name "OUT21_P") (class "Default")
      (node (ref "X-EAST") (pin "61") (pinfunction "61_61") (pintype "bidirectional"))
      (node (ref "X-SOUTH") (pin "61") (pinfunction "61_61") (pintype "bidirectional"))
    )
    (net (code "82") (name "OUT22_N") (class "Default")
      (node (ref "X-SOUTH") (pin "60") (pinfunction "60_60") (pintype "bidirectional"))
    )
    (net (code "83") (name "OUT22_P") (class "Default")
      (node (ref "X-SOUTH") (pin "58") (pinfunction "58_58") (pintype "bidirectional"))
    )
    (net (code "84") (name "OUT23_N") (class "Default")
      (node (ref "X-EAST") (pin "66") (pinfunction "66_66") (pintype "bidirectional"))
      (node (ref "X-SOUTH") (pin "54") (pinfunction "54_54") (pintype "bidirectional"))
    )
    (net (code "85") (name "OUT23_P") (class "Default")
      (node (ref "X-EAST") (pin "68") (pinfunction "68_68") (pintype "bidirectional"))
      (node (ref "X-SOUTH") (pin "52") (pinfunction "52_52") (pintype "bidirectional"))
    )
    (net (code "86") (name "OUT24_N") (class "Default")
      (node (ref "X-SOUTH") (pin "51") (pinfunction "51_51") (pintype "bidirectional"))
    )
    (net (code "87") (name "OUT24_P") (class "Default")
      (node (ref "X-SOUTH") (pin "49") (pinfunction "49_49") (pintype "bidirectional"))
    )
    (net (code "88") (name "OUT25_N") (class "Default")
      (node (ref "X-EAST") (pin "65") (pinfunction "65_65") (pintype "bidirectional"))
      (node (ref "X-SOUTH") (pin "57") (pinfunction "57_57") (pintype "bidirectional"))
    )
    (net (code "89") (name "OUT25_P") (class "Default")
      (node (ref "X-EAST") (pin "67") (pinfunction "67_67") (pintype "bidirectional"))
      (node (ref "X-SOUTH") (pin "55") (pinfunction "55_55") (pintype "bidirectional"))
    )
    (net (code "90") (name "OUT26_N") (class "Default")
      (node (ref "X-SOUTH") (pin "48") (pinfunction "48_48") (pintype "bidirectional"))
    )
    (net (code "91") (name "OUT26_P") (class "Default")
      (node (ref "X-SOUTH") (pin "46") (pinfunction "46_46") (pintype "bidirectional"))
    )
    (net (code "92") (name "OUT27_N") (class "Default")
      (node (ref "X-EAST") (pin "73") (pinfunction "73_73") (pintype "bidirectional"))
      (node (ref "X-SOUTH") (pin "39") (pinfunction "39_39") (pintype "bidirectional"))
    )
    (net (code "93") (name "OUT27_P") (class "Default")
      (node (ref "X-EAST") (pin "75") (pinfunction "75_75") (pintype "bidirectional"))
      (node (ref "X-SOUTH") (pin "37") (pinfunction "37_37") (pintype "bidirectional"))
    )
    (net (code "94") (name "OUT28_N") (class "Default")
      (node (ref "X-SOUTH") (pin "45") (pinfunction "45_45") (pintype "bidirectional"))
    )
    (net (code "95") (name "OUT28_P") (class "Default")
      (node (ref "X-SOUTH") (pin "43") (pinfunction "43_43") (pintype "bidirectional"))
    )
    (net (code "96") (name "OUT29_N") (class "Default")
      (node (ref "X-EAST") (pin "72") (pinfunction "72_72") (pintype "bidirectional"))
      (node (ref "X-SOUTH") (pin "42") (pinfunction "42_42") (pintype "bidirectional"))
    )
    (net (code "97") (name "OUT29_P") (class "Default")
      (node (ref "X-EAST") (pin "74") (pinfunction "74_74") (pintype "bidirectional"))
      (node (ref "X-SOUTH") (pin "40") (pinfunction "40_40") (pintype "bidirectional"))
    )
    (net (code "98") (name "OUT30_N") (class "Default")
      (node (ref "X-SOUTH") (pin "33") (pinfunction "33_33") (pintype "bidirectional"))
    )
    (net (code "99") (name "OUT30_P") (class "Default")
      (node (ref "X-SOUTH") (pin "31") (pinfunction "31_31") (pintype "bidirectional"))
    )
    (net (code "100") (name "OUT31_N") (class "Default")
      (node (ref "X-EAST") (pin "78") (pinfunction "78_78") (pintype "bidirectional"))
      (node (ref "X-SOUTH") (pin "36") (pinfunction "36_36") (pintype "bidirectional"))
    )
    (net (code "101") (name "OUT31_P") (class "Default")
      (node (ref "X-EAST") (pin "80") (pinfunction "80_80") (pintype "bidirectional"))
      (node (ref "X-SOUTH") (pin "34") (pinfunction "34_34") (pintype "bidirectional"))
    )
    (net (code "102") (name "OUT32_N") (class "Default")
      (node (ref "X-SOUTH") (pin "27") (pinfunction "27_27") (pintype "bidirectional"))
    )
    (net (code "103") (name "OUT32_P") (class "Default")
      (node (ref "X-SOUTH") (pin "25") (pinfunction "25_25") (pintype "bidirectional"))
    )
    (net (code "104") (name "OUT33_N") (class "Default")
      (node (ref "X-NORTH") (pin "19") (pinfunction "19_19") (pintype "bidirectional"))
      (node (ref "X-WEST") (pin "67") (pinfunction "67_67") (pintype "bidirectional"))
    )
    (net (code "105") (name "OUT33_P") (class "Default")
      (node (ref "X-NORTH") (pin "21") (pinfunction "21_21") (pintype "bidirectional"))
      (node (ref "X-WEST") (pin "65") (pinfunction "65_65") (pintype "bidirectional"))
    )
    (net (code "106") (name "OUT34_N") (class "Default")
      (node (ref "X-NORTH") (pin "28") (pinfunction "28_28") (pintype "bidirectional"))
    )
    (net (code "107") (name "OUT34_P") (class "Default")
      (node (ref "X-NORTH") (pin "30") (pinfunction "30_30") (pintype "bidirectional"))
    )
    (net (code "108") (name "OUT35_N") (class "Default")
      (node (ref "X-NORTH") (pin "25") (pinfunction "25_25") (pintype "bidirectional"))
      (node (ref "X-WEST") (pin "61") (pinfunction "61_61") (pintype "bidirectional"))
    )
    (net (code "109") (name "OUT35_P") (class "Default")
      (node (ref "X-NORTH") (pin "27") (pinfunction "27_27") (pintype "bidirectional"))
      (node (ref "X-WEST") (pin "59") (pinfunction "59_59") (pintype "bidirectional"))
    )
    (net (code "110") (name "OUT36_N") (class "Default")
      (node (ref "X-NORTH") (pin "34") (pinfunction "34_34") (pintype "bidirectional"))
    )
    (net (code "111") (name "OUT36_P") (class "Default")
      (node (ref "X-NORTH") (pin "36") (pinfunction "36_36") (pintype "bidirectional"))
    )
    (net (code "112") (name "OUT37_N") (class "Default")
      (node (ref "X-NORTH") (pin "31") (pinfunction "31_31") (pintype "bidirectional"))
      (node (ref "X-WEST") (pin "47") (pinfunction "47_47") (pintype "bidirectional"))
    )
    (net (code "113") (name "OUT37_P") (class "Default")
      (node (ref "X-NORTH") (pin "33") (pinfunction "33_33") (pintype "bidirectional"))
      (node (ref "X-WEST") (pin "45") (pinfunction "45_45") (pintype "bidirectional"))
    )
    (net (code "114") (name "OUT38_N") (class "Default")
      (node (ref "X-NORTH") (pin "37") (pinfunction "37_37") (pintype "bidirectional"))
    )
    (net (code "115") (name "OUT38_P") (class "Default")
      (node (ref "X-NORTH") (pin "39") (pinfunction "39_39") (pintype "bidirectional"))
    )
    (net (code "116") (name "OUT39_N") (class "Default")
      (node (ref "X-NORTH") (pin "40") (pinfunction "40_40") (pintype "bidirectional"))
      (node (ref "X-WEST") (pin "80") (pinfunction "80_80") (pintype "bidirectional"))
    )
    (net (code "117") (name "OUT39_P") (class "Default")
      (node (ref "X-NORTH") (pin "42") (pinfunction "42_42") (pintype "bidirectional"))
      (node (ref "X-WEST") (pin "78") (pinfunction "78_78") (pintype "bidirectional"))
    )
    (net (code "118") (name "OUT40_N") (class "Default")
      (node (ref "X-NORTH") (pin "43") (pinfunction "43_43") (pintype "bidirectional"))
    )
    (net (code "119") (name "OUT40_P") (class "Default")
      (node (ref "X-NORTH") (pin "45") (pinfunction "45_45") (pintype "bidirectional"))
    )
    (net (code "120") (name "OUT41_N") (class "Default")
      (node (ref "X-NORTH") (pin "46") (pinfunction "46_46") (pintype "bidirectional"))
      (node (ref "X-WEST") (pin "74") (pinfunction "74_74") (pintype "bidirectional"))
    )
    (net (code "121") (name "OUT41_P") (class "Default")
      (node (ref "X-NORTH") (pin "48") (pinfunction "48_48") (pintype "bidirectional"))
      (node (ref "X-WEST") (pin "72") (pinfunction "72_72") (pintype "bidirectional"))
    )
    (net (code "122") (name "OUT42_N") (class "Default")
      (node (ref "X-NORTH") (pin "49") (pinfunction "49_49") (pintype "bidirectional"))
    )
    (net (code "123") (name "OUT42_P") (class "Default")
      (node (ref "X-NORTH") (pin "51") (pinfunction "51_51") (pintype "bidirectional"))
    )
    (net (code "124") (name "OUT43_N") (class "Default")
      (node (ref "X-NORTH") (pin "52") (pinfunction "52_52") (pintype "bidirectional"))
      (node (ref "X-WEST") (pin "68") (pinfunction "68_68") (pintype "bidirectional"))
    )
    (net (code "125") (name "OUT43_P") (class "Default")
      (node (ref "X-NORTH") (pin "54") (pinfunction "54_54") (pintype "bidirectional"))
      (node (ref "X-WEST") (pin "66") (pinfunction "66_66") (pintype "bidirectional"))
    )
    (net (code "126") (name "OUT44_N") (class "Default")
      (node (ref "X-NORTH") (pin "55") (pinfunction "55_55") (pintype "bidirectional"))
    )
    (net (code "127") (name "OUT44_P") (class "Default")
      (node (ref "X-NORTH") (pin "57") (pinfunction "57_57") (pintype "bidirectional"))
    )
    (net (code "128") (name "OUT45_N") (class "Default")
      (node (ref "X-NORTH") (pin "58") (pinfunction "58_58") (pintype "bidirectional"))
      (node (ref "X-WEST") (pin "62") (pinfunction "62_62") (pintype "bidirectional"))
    )
    (net (code "129") (name "OUT45_P") (class "Default")
      (node (ref "X-NORTH") (pin "60") (pinfunction "60_60") (pintype "bidirectional"))
      (node (ref "X-WEST") (pin "60") (pinfunction "60_60") (pintype "bidirectional"))
    )
    (net (code "130") (name "OUT46_N") (class "Default")
      (node (ref "X-NORTH") (pin "61") (pinfunction "61_61") (pintype "bidirectional"))
    )
    (net (code "131") (name "OUT46_P") (class "Default")
      (node (ref "X-NORTH") (pin "63") (pinfunction "63_63") (pintype "bidirectional"))
    )
    (net (code "132") (name "OUT47_N") (class "Default")
      (node (ref "X-NORTH") (pin "64") (pinfunction "64_64") (pintype "bidirectional"))
      (node (ref "X-WEST") (pin "56") (pinfunction "56_56") (pintype "bidirectional"))
    )
    (net (code "133") (name "OUT47_P") (class "Default")
      (node (ref "X-NORTH") (pin "66") (pinfunction "66_66") (pintype "bidirectional"))
      (node (ref "X-WEST") (pin "54") (pinfunction "54_54") (pintype "bidirectional"))
    )
    (net (code "134") (name "OUT48_N") (class "Default")
      (node (ref "X-NORTH") (pin "67") (pinfunction "67_67") (pintype "bidirectional"))
    )
    (net (code "135") (name "OUT48_P") (class "Default")
      (node (ref "X-NORTH") (pin "69") (pinfunction "69_69") (pintype "bidirectional"))
    )
    (net (code "136") (name "OUT49_N") (class "Default")
      (node (ref "X-EAST") (pin "48") (pinfunction "48_48") (pintype "bidirectional"))
      (node (ref "X-NORTH") (pin "73") (pinfunction "73_73") (pintype "bidirectional"))
    )
    (net (code "137") (name "OUT49_P") (class "Default")
      (node (ref "X-EAST") (pin "46") (pinfunction "46_46") (pintype "bidirectional"))
      (node (ref "X-NORTH") (pin "75") (pinfunction "75_75") (pintype "bidirectional"))
    )
    (net (code "138") (name "OUT50_N") (class "Default")
      (node (ref "X-NORTH") (pin "70") (pinfunction "70_70") (pintype "bidirectional"))
    )
    (net (code "139") (name "OUT50_P") (class "Default")
      (node (ref "X-NORTH") (pin "72") (pinfunction "72_72") (pintype "bidirectional"))
    )
    (net (code "140") (name "OUT51_N") (class "Default")
      (node (ref "X-EAST") (pin "42") (pinfunction "42_42") (pintype "bidirectional"))
      (node (ref "X-NORTH") (pin "79") (pinfunction "79_79") (pintype "bidirectional"))
    )
    (net (code "141") (name "OUT51_P") (class "Default")
      (node (ref "X-EAST") (pin "40") (pinfunction "40_40") (pintype "bidirectional"))
      (node (ref "X-NORTH") (pin "81") (pinfunction "81_81") (pintype "bidirectional"))
    )
    (net (code "142") (name "OUT52_N") (class "Default")
      (node (ref "X-NORTH") (pin "76") (pinfunction "76_76") (pintype "bidirectional"))
    )
    (net (code "143") (name "OUT52_P") (class "Default")
      (node (ref "X-NORTH") (pin "78") (pinfunction "78_78") (pintype "bidirectional"))
    )
    (net (code "144") (name "OUT53_N") (class "Default")
      (node (ref "X-EAST") (pin "47") (pinfunction "47_47") (pintype "bidirectional"))
      (node (ref "X-NORTH") (pin "85") (pinfunction "85_85") (pintype "bidirectional"))
    )
    (net (code "145") (name "OUT53_P") (class "Default")
      (node (ref "X-EAST") (pin "45") (pinfunction "45_45") (pintype "bidirectional"))
      (node (ref "X-NORTH") (pin "87") (pinfunction "87_87") (pintype "bidirectional"))
    )
    (net (code "146") (name "OUT54_N") (class "Default")
      (node (ref "X-NORTH") (pin "82") (pinfunction "82_82") (pintype "bidirectional"))
    )
    (net (code "147") (name "OUT54_P") (class "Default")
      (node (ref "X-NORTH") (pin "84") (pinfunction "84_84") (pintype "bidirectional"))
    )
    (net (code "148") (name "OUT55_N") (class "Default")
      (node (ref "X-EAST") (pin "41") (pinfunction "41_41") (pintype "bidirectional"))
      (node (ref "X-NORTH") (pin "91") (pinfunction "91_91") (pintype "bidirectional"))
    )
    (net (code "149") (name "OUT55_P") (class "Default")
      (node (ref "X-EAST") (pin "39") (pinfunction "39_39") (pintype "bidirectional"))
      (node (ref "X-NORTH") (pin "93") (pinfunction "93_93") (pintype "bidirectional"))
    )
    (net (code "150") (name "OUT56_N") (class "Default")
      (node (ref "X-NORTH") (pin "88") (pinfunction "88_88") (pintype "bidirectional"))
    )
    (net (code "151") (name "OUT56_P") (class "Default")
      (node (ref "X-NORTH") (pin "90") (pinfunction "90_90") (pintype "bidirectional"))
    )
    (net (code "152") (name "OUT57_N") (class "Default")
      (node (ref "X-EAST") (pin "35") (pinfunction "35_35") (pintype "bidirectional"))
      (node (ref "X-NORTH") (pin "97") (pinfunction "97_97") (pintype "bidirectional"))
    )
    (net (code "153") (name "OUT57_P") (class "Default")
      (node (ref "X-EAST") (pin "33") (pinfunction "33_33") (pintype "bidirectional"))
      (node (ref "X-NORTH") (pin "99") (pinfunction "99_99") (pintype "bidirectional"))
    )
    (net (code "154") (name "OUT58_N") (class "Default")
      (node (ref "X-NORTH") (pin "94") (pinfunction "94_94") (pintype "bidirectional"))
    )
    (net (code "155") (name "OUT58_P") (class "Default")
      (node (ref "X-NORTH") (pin "96") (pinfunction "96_96") (pintype "bidirectional"))
    )
    (net (code "156") (name "OUT59_N") (class "Default")
      (node (ref "X-EAST") (pin "27") (pinfunction "27_27") (pintype "bidirectional"))
      (node (ref "X-NORTH") (pin "103") (pinfunction "103_103") (pintype "bidirectional"))
    )
    (net (code "157") (name "OUT59_P") (class "Default")
      (node (ref "X-EAST") (pin "25") (pinfunction "25_25") (pintype "bidirectional"))
      (node (ref "X-NORTH") (pin "105") (pinfunction "105_105") (pintype "bidirectional"))
    )
    (net (code "158") (name "OUT60_N") (class "Default")
      (node (ref "X-NORTH") (pin "109") (pinfunction "109_109") (pintype "bidirectional"))
    )
    (net (code "159") (name "OUT60_P") (class "Default")
      (node (ref "X-NORTH") (pin "111") (pinfunction "111_111") (pintype "bidirectional"))
    )
    (net (code "160") (name "OUT61_N") (class "Default")
      (node (ref "X-EAST") (pin "36") (pinfunction "36_36") (pintype "bidirectional"))
      (node (ref "X-NORTH") (pin "100") (pinfunction "100_100") (pintype "bidirectional"))
    )
    (net (code "161") (name "OUT61_P") (class "Default")
      (node (ref "X-EAST") (pin "34") (pinfunction "34_34") (pintype "bidirectional"))
      (node (ref "X-NORTH") (pin "102") (pinfunction "102_102") (pintype "bidirectional"))
    )
    (net (code "162") (name "OUT62_N") (class "Default")
      (node (ref "X-NORTH") (pin "115") (pinfunction "115_115") (pintype "bidirectional"))
    )
    (net (code "163") (name "OUT62_P") (class "Default")
      (node (ref "X-NORTH") (pin "117") (pinfunction "117_117") (pintype "bidirectional"))
    )
    (net (code "164") (name "OUT63_N") (class "Default")
      (node (ref "X-EAST") (pin "30") (pinfunction "30_30") (pintype "bidirectional"))
      (node (ref "X-NORTH") (pin "106") (pinfunction "106_106") (pintype "bidirectional"))
    )
    (net (code "165") (name "OUT63_P") (class "Default")
      (node (ref "X-EAST") (pin "28") (pinfunction "28_28") (pintype "bidirectional"))
      (node (ref "X-NORTH") (pin "108") (pinfunction "108_108") (pintype "bidirectional"))
    )
    (net (code "166") (name "OUT64_N") (class "Default")
      (node (ref "X-NORTH") (pin "112") (pinfunction "112_112") (pintype "bidirectional"))
    )
    (net (code "167") (name "OUT64_P") (class "Default")
      (node (ref "X-NORTH") (pin "114") (pinfunction "114_114") (pintype "bidirectional"))
    )
    (net (code "168") (name "OUTCLK_N") (class "Default")
      (node (ref "X-NORTH") (pin "16") (pinfunction "16_16") (pintype "bidirectional"))
      (node (ref "X-WEST") (pin "53") (pinfunction "53_53") (pintype "bidirectional"))
    )
    (net (code "169") (name "OUTCLK_P") (class "Default")
      (node (ref "X-NORTH") (pin "18") (pinfunction "18_18") (pintype "bidirectional"))
      (node (ref "X-WEST") (pin "55") (pinfunction "55_55") (pintype "bidirectional"))
    )
    (net (code "170") (name "OUTCTR_N") (class "Default")
      (node (ref "X-SOUTH") (pin "126") (pinfunction "126_126") (pintype "bidirectional"))
      (node (ref "X-WEST") (pin "22") (pinfunction "22_22") (pintype "bidirectional"))
    )
    (net (code "171") (name "OUTCTR_P") (class "Default")
      (node (ref "X-SOUTH") (pin "124") (pinfunction "124_124") (pintype "bidirectional"))
      (node (ref "X-WEST") (pin "24") (pinfunction "24_24") (pintype "bidirectional"))
    )
    (net (code "172") (name "S00_N") (class "Default")
      (node (ref "X-SOUTH") (pin "15") (pinfunction "15_15") (pintype "bidirectional"))
    )
    (net (code "173") (name "S00_P") (class "Default")
      (node (ref "X-SOUTH") (pin "13") (pinfunction "13_13") (pintype "bidirectional"))
    )
    (net (code "174") (name "S01_N") (class "Default")
      (node (ref "X-SOUTH") (pin "18") (pinfunction "18_18") (pintype "bidirectional"))
    )
    (net (code "175") (name "S01_P") (class "Default")
      (node (ref "X-SOUTH") (pin "16") (pinfunction "16_16") (pintype "bidirectional"))
    )
    (net (code "176") (name "S02_N") (class "Default")
      (node (ref "X-SOUTH") (pin "21") (pinfunction "21_21") (pintype "bidirectional"))
    )
    (net (code "177") (name "S02_P") (class "Default")
      (node (ref "X-SOUTH") (pin "19") (pinfunction "19_19") (pintype "bidirectional"))
    )
    (net (code "178") (name "S03_N") (class "Default")
      (node (ref "X-SOUTH") (pin "24") (pinfunction "24_24") (pintype "bidirectional"))
    )
    (net (code "179") (name "S03_P") (class "Default")
      (node (ref "X-SOUTH") (pin "22") (pinfunction "22_22") (pintype "bidirectional"))
    )
    (net (code "180") (name "S05_N") (class "Default")
      (node (ref "X-SOUTH") (pin "30") (pinfunction "30_30") (pintype "bidirectional"))
    )
    (net (code "181") (name "S05_P") (class "Default")
      (node (ref "X-SOUTH") (pin "28") (pinfunction "28_28") (pintype "bidirectional"))
    )
    (net (code "182") (name "S38_N") (class "Default")
      (node (ref "X-SOUTH") (pin "129") (pinfunction "129_129") (pintype "bidirectional"))
    )
    (net (code "183") (name "S38_P") (class "Default")
      (node (ref "X-SOUTH") (pin "127") (pinfunction "127_127") (pintype "bidirectional"))
    )
    (net (code "184") (name "S39_N") (class "Default")
      (node (ref "X-SOUTH") (pin "132") (pinfunction "132_132") (pintype "bidirectional"))
    )
    (net (code "185") (name "S39_P") (class "Default")
      (node (ref "X-SOUTH") (pin "130") (pinfunction "130_130") (pintype "bidirectional"))
    )
    (net (code "186") (name "SPI_EN") (class "Default")
      (node (ref "X-EAST") (pin "14") (pinfunction "14_14") (pintype "bidirectional"))
      (node (ref "X-NORTH") (pin "120") (pinfunction "120_120") (pintype "bidirectional"))
    )
    (net (code "187") (name "SYS_RES_N") (class "Default")
      (node (ref "X-EAST") (pin "22") (pinfunction "22_22") (pintype "bidirectional"))
      (node (ref "X-NORTH") (pin "126") (pinfunction "126_126") (pintype "bidirectional"))
    )
    (net (code "188") (name "S_CHK_V") (class "Default")
      (node (ref "X-EAST") (pin "92") (pinfunction "92_92") (pintype "bidirectional"))
      (node (ref "X-EAST") (pin "94") (pinfunction "94_94") (pintype "bidirectional"))
      (node (ref "X-SOUTH") (pin "7") (pinfunction "7_7") (pintype "bidirectional"))
      (node (ref "X-SOUTH") (pin "9") (pinfunction "9_9") (pintype "bidirectional"))
    )
    (net (code "189") (name "S_I2C_V") (class "Default")
      (node (ref "X-SOUTH") (pin "136") (pinfunction "136_136") (pintype "bidirectional"))
      (node (ref "X-SOUTH") (pin "138") (pinfunction "138_138") (pintype "bidirectional"))
      (node (ref "X-WEST") (pin "7") (pinfunction "7_7") (pintype "bidirectional"))
      (node (ref "X-WEST") (pin "9") (pinfunction "9_9") (pintype "bidirectional"))
    )
    (net (code "190") (name "S_SCK") (class "Default")
      (node (ref "X-SOUTH") (pin "143") (pinfunction "143_143") (pintype "bidirectional"))
      (node (ref "X-WEST") (pin "2") (pinfunction "2_2") (pintype "bidirectional"))
    )
    (net (code "191") (name "S_SCL") (class "Default")
      (node (ref "X-SOUTH") (pin "144") (pinfunction "144_144") (pintype "bidirectional"))
      (node (ref "X-WEST") (pin "1") (pinfunction "1_1") (pintype "bidirectional"))
    )
    (net (code "192") (name "S_SDA") (class "Default")
      (node (ref "X-SOUTH") (pin "142") (pinfunction "142_142") (pintype "bidirectional"))
      (node (ref "X-WEST") (pin "3") (pinfunction "3_3") (pintype "bidirectional"))
    )
    (net (code "193") (name "S_SDI") (class "Default")
      (node (ref "X-SOUTH") (pin "139") (pinfunction "139_139") (pintype "bidirectional"))
      (node (ref "X-WEST") (pin "6") (pinfunction "6_6") (pintype "bidirectional"))
    )
    (net (code "194") (name "S_SDO") (class "Default")
      (node (ref "X-SOUTH") (pin "141") (pinfunction "141_141") (pintype "bidirectional"))
      (node (ref "X-WEST") (pin "4") (pinfunction "4_4") (pintype "bidirectional"))
    )
    (net (code "195") (name "S_SPI_V") (class "Default")
      (node (ref "X-SOUTH") (pin "133") (pinfunction "133_133") (pintype "bidirectional"))
      (node (ref "X-SOUTH") (pin "135") (pinfunction "135_135") (pintype "bidirectional"))
      (node (ref "X-WEST") (pin "10") (pinfunction "10_10") (pintype "bidirectional"))
      (node (ref "X-WEST") (pin "8") (pinfunction "8_8") (pintype "bidirectional"))
    )
    (net (code "196") (name "S_VE") (class "Default")
      (node (ref "C7") (pin "1") (pinfunction "1_1") (pintype "passive"))
      (node (ref "P-E") (pin "5") (pinfunction "5_5") (pintype "passive"))
      (node (ref "X-EAST") (pin "51") (pinfunction "51_51") (pintype "bidirectional"))
      (node (ref "X-EAST") (pin "57") (pinfunction "57_57") (pintype "bidirectional"))
      (node (ref "X-EAST") (pin "63") (pinfunction "63_63") (pintype "bidirectional"))
      (node (ref "X-EAST") (pin "69") (pinfunction "69_69") (pintype "bidirectional"))
      (node (ref "X-SOUTH") (pin "14") (pinfunction "14_14") (pintype "bidirectional"))
      (node (ref "X-SOUTH") (pin "20") (pinfunction "20_20") (pintype "bidirectional"))
      (node (ref "X-SOUTH") (pin "26") (pinfunction "26_26") (pintype "bidirectional"))
      (node (ref "X-SOUTH") (pin "32") (pinfunction "32_32") (pintype "bidirectional"))
      (node (ref "X-SOUTH") (pin "38") (pinfunction "38_38") (pintype "bidirectional"))
    )
    (net (code "197") (name "S_VE_CV") (class "Default")
      (node (ref "X-EAST") (pin "100") (pinfunction "100_100") (pintype "bidirectional"))
      (node (ref "X-SOUTH") (pin "1") (pinfunction "1_1") (pintype "bidirectional"))
    )
    (net (code "198") (name "S_VE_OV") (class "Default")
      (node (ref "X-EAST") (pin "99") (pinfunction "99_99") (pintype "bidirectional"))
      (node (ref "X-SOUTH") (pin "2") (pinfunction "2_2") (pintype "bidirectional"))
    )
    (net (code "199") (name "S_VE_UV") (class "Default")
      (node (ref "X-EAST") (pin "89") (pinfunction "89_89") (pintype "bidirectional"))
      (node (ref "X-SOUTH") (pin "8") (pinfunction "8_8") (pintype "bidirectional"))
    )
    (net (code "200") (name "S_VS") (class "Default")
      (node (ref "C6") (pin "1") (pinfunction "1_1") (pintype "passive"))
      (node (ref "P-E") (pin "3") (pinfunction "3_3") (pintype "passive"))
      (node (ref "X-EAST") (pin "32") (pinfunction "32_32") (pintype "bidirectional"))
      (node (ref "X-EAST") (pin "38") (pinfunction "38_38") (pintype "bidirectional"))
      (node (ref "X-EAST") (pin "44") (pinfunction "44_44") (pintype "bidirectional"))
      (node (ref "X-EAST") (pin "50") (pinfunction "50_50") (pintype "bidirectional"))
      (node (ref "X-EAST") (pin "52") (pinfunction "52_52") (pintype "bidirectional"))
      (node (ref "X-EAST") (pin "58") (pinfunction "58_58") (pintype "bidirectional"))
      (node (ref "X-EAST") (pin "64") (pinfunction "64_64") (pintype "bidirectional"))
      (node (ref "X-EAST") (pin "70") (pinfunction "70_70") (pintype "bidirectional"))
      (node (ref "X-SOUTH") (pin "50") (pinfunction "50_50") (pintype "bidirectional"))
      (node (ref "X-SOUTH") (pin "56") (pinfunction "56_56") (pintype "bidirectional"))
      (node (ref "X-SOUTH") (pin "62") (pinfunction "62_62") (pintype "bidirectional"))
      (node (ref "X-SOUTH") (pin "68") (pinfunction "68_68") (pintype "bidirectional"))
      (node (ref "X-SOUTH") (pin "74") (pinfunction "74_74") (pintype "bidirectional"))
      (node (ref "X-SOUTH") (pin "80") (pinfunction "80_80") (pintype "bidirectional"))
      (node (ref "X-SOUTH") (pin "86") (pinfunction "86_86") (pintype "bidirectional"))
      (node (ref "X-SOUTH") (pin "92") (pinfunction "92_92") (pintype "bidirectional"))
      (node (ref "X-SOUTH") (pin "98") (pinfunction "98_98") (pintype "bidirectional"))
    )
    (net (code "201") (name "S_VS_CV") (class "Default")
      (node (ref "X-EAST") (pin "98") (pinfunction "98_98") (pintype "bidirectional"))
      (node (ref "X-SOUTH") (pin "3") (pinfunction "3_3") (pintype "bidirectional"))
    )
    (net (code "202") (name "S_VS_OV") (class "Default")
      (node (ref "X-EAST") (pin "97") (pinfunction "97_97") (pintype "bidirectional"))
      (node (ref "X-SOUTH") (pin "4") (pinfunction "4_4") (pintype "bidirectional"))
    )
    (net (code "203") (name "S_VS_UV") (class "Default")
      (node (ref "X-EAST") (pin "87") (pinfunction "87_87") (pintype "bidirectional"))
      (node (ref "X-SOUTH") (pin "10") (pinfunction "10_10") (pintype "bidirectional"))
    )
    (net (code "204") (name "S_VW") (class "Default")
      (node (ref "C2") (pin "1") (pinfunction "1_1") (pintype "passive"))
      (node (ref "P-W") (pin "1") (pinfunction "1_1") (pintype "passive"))
      (node (ref "X-SOUTH") (pin "110") (pinfunction "110_110") (pintype "bidirectional"))
      (node (ref "X-SOUTH") (pin "116") (pinfunction "116_116") (pintype "bidirectional"))
      (node (ref "X-SOUTH") (pin "122") (pinfunction "122_122") (pintype "bidirectional"))
      (node (ref "X-SOUTH") (pin "128") (pinfunction "128_128") (pintype "bidirectional"))
      (node (ref "X-SOUTH") (pin "134") (pinfunction "134_134") (pintype "bidirectional"))
      (node (ref "X-WEST") (pin "31") (pinfunction "31_31") (pintype "bidirectional"))
      (node (ref "X-WEST") (pin "37") (pinfunction "37_37") (pintype "bidirectional"))
      (node (ref "X-WEST") (pin "43") (pinfunction "43_43") (pintype "bidirectional"))
      (node (ref "X-WEST") (pin "49") (pinfunction "49_49") (pintype "bidirectional"))
    )
    (net (code "205") (name "S_VW_CV") (class "Default")
      (node (ref "X-EAST") (pin "96") (pinfunction "96_96") (pintype "bidirectional"))
      (node (ref "X-SOUTH") (pin "5") (pinfunction "5_5") (pintype "bidirectional"))
    )
    (net (code "206") (name "S_VW_OV") (class "Default")
      (node (ref "X-EAST") (pin "95") (pinfunction "95_95") (pintype "bidirectional"))
      (node (ref "X-SOUTH") (pin "6") (pinfunction "6_6") (pintype "bidirectional"))
    )
    (net (code "207") (name "S_VW_UV") (class "Default")
      (node (ref "X-EAST") (pin "85") (pinfunction "85_85") (pintype "bidirectional"))
      (node (ref "X-SOUTH") (pin "12") (pinfunction "12_12") (pintype "bidirectional"))
    )
    (net (code "208") (name "TCK") (class "Default")
      (node (ref "X-WEST") (pin "12") (pinfunction "12_12") (pintype "bidirectional"))
    )
    (net (code "209") (name "TDI") (class "Default")
      (node (ref "X-WEST") (pin "16") (pinfunction "16_16") (pintype "bidirectional"))
    )
    (net (code "210") (name "TDIG1") (class "Default")
      (node (ref "X-EAST") (pin "18") (pinfunction "18_18") (pintype "bidirectional"))
      (node (ref "X-NORTH") (pin "124") (pinfunction "124_124") (pintype "bidirectional"))
    )
    (net (code "211") (name "TDIG2") (class "Default")
      (node (ref "X-EAST") (pin "17") (pinfunction "17_17") (pintype "bidirectional"))
      (node (ref "X-NORTH") (pin "129") (pinfunction "129_129") (pintype "bidirectional"))
    )
    (net (code "212") (name "TDO") (class "Default")
      (node (ref "X-WEST") (pin "18") (pinfunction "18_18") (pintype "bidirectional"))
    )
    (net (code "213") (name "TMS") (class "Default")
      (node (ref "X-WEST") (pin "14") (pinfunction "14_14") (pintype "bidirectional"))
    )
    (net (code "214") (name "T_EXP1") (class "Default")
      (node (ref "X-EAST") (pin "12") (pinfunction "12_12") (pintype "bidirectional"))
      (node (ref "X-NORTH") (pin "132") (pinfunction "132_132") (pintype "bidirectional"))
    )
    (net (code "215") (name "T_EXP2") (class "Default")
      (node (ref "X-EAST") (pin "16") (pinfunction "16_16") (pintype "bidirectional"))
      (node (ref "X-NORTH") (pin "118") (pinfunction "118_118") (pintype "bidirectional"))
    )
    (net (code "216") (name "W_I2C_V") (class "Default")
      (node (ref "X-WEST") (pin "11") (pinfunction "11_11") (pintype "bidirectional"))
      (node (ref "X-WEST") (pin "13") (pinfunction "13_13") (pintype "bidirectional"))
    )
    (net (code "217") (name "W_SCL") (class "Default")
      (node (ref "X-WEST") (pin "15") (pinfunction "15_15") (pintype "bidirectional"))
    )
    (net (code "218") (name "W_SDA") (class "Default")
      (node (ref "X-WEST") (pin "17") (pinfunction "17_17") (pintype "bidirectional"))
    )
    (net (code "219") (name "W_VW") (class "Default")
      (node (ref "X-WEST") (pin "79") (pinfunction "79_79") (pintype "bidirectional"))
      (node (ref "X-WEST") (pin "81") (pinfunction "81_81") (pintype "bidirectional"))
      (node (ref "X-WEST") (pin "83") (pinfunction "83_83") (pintype "bidirectional"))
      (node (ref "X-WEST") (pin "84") (pinfunction "84_84") (pintype "bidirectional"))
      (node (ref "X-WEST") (pin "86") (pinfunction "86_86") (pintype "bidirectional"))
      (node (ref "X-WEST") (pin "88") (pinfunction "88_88") (pintype "bidirectional"))
    )
    (net (code "220") (name "W_VW_CV") (class "Default")
      (node (ref "X-WEST") (pin "90") (pinfunction "90_90") (pintype "bidirectional"))
    )
    (net (code "221") (name "W_VW_OV") (class "Default")
      (node (ref "X-WEST") (pin "93") (pinfunction "93_93") (pintype "bidirectional"))
    )
    (net (code "222") (name "W_VW_UV") (class "Default")
      (node (ref "X-WEST") (pin "91") (pinfunction "91_91") (pintype "bidirectional"))
    )
    (net (code "223") (name "unconnected-(X-EAST-PadM1)") (class "Default")
      (node (ref "X-EAST") (pin "M1") (pinfunction "M1_M1") (pintype "bidirectional"))
    )
    (net (code "224") (name "unconnected-(X-EAST-PadM2)") (class "Default")
      (node (ref "X-EAST") (pin "M2") (pinfunction "M2_M2") (pintype "bidirectional"))
    )
    (net (code "225") (name "unconnected-(X-NORTH-PadM1)") (class "Default")
      (node (ref "X-NORTH") (pin "M1") (pinfunction "M1_M1") (pintype "bidirectional"))
    )
    (net (code "226") (name "unconnected-(X-NORTH-PadM2)") (class "Default")
      (node (ref "X-NORTH") (pin "M2") (pinfunction "M2_M2") (pintype "bidirectional"))
    )
    (net (code "227") (name "unconnected-(X-SOUTH-PadM1)") (class "Default")
      (node (ref "X-SOUTH") (pin "M1") (pinfunction "M1_M1") (pintype "bidirectional"))
    )
    (net (code "228") (name "unconnected-(X-SOUTH-PadM2)") (class "Default")
      (node (ref "X-SOUTH") (pin "M2") (pinfunction "M2_M2") (pintype "bidirectional"))
    )
    (net (code "229") (name "unconnected-(X-WEST-PadM1)") (class "Default")
      (node (ref "X-WEST") (pin "M1") (pinfunction "M1_M1") (pintype "bidirectional"))
    )
    (net (code "230") (name "unconnected-(X-WEST-PadM2)") (class "Default")
      (node (ref "X-WEST") (pin "M2") (pinfunction "M2_M2") (pintype "bidirectional"))
    )
  )
)
